# 12_MEM_DDR3.net
KiCad netlist of a schematic drawn in Altium Designer
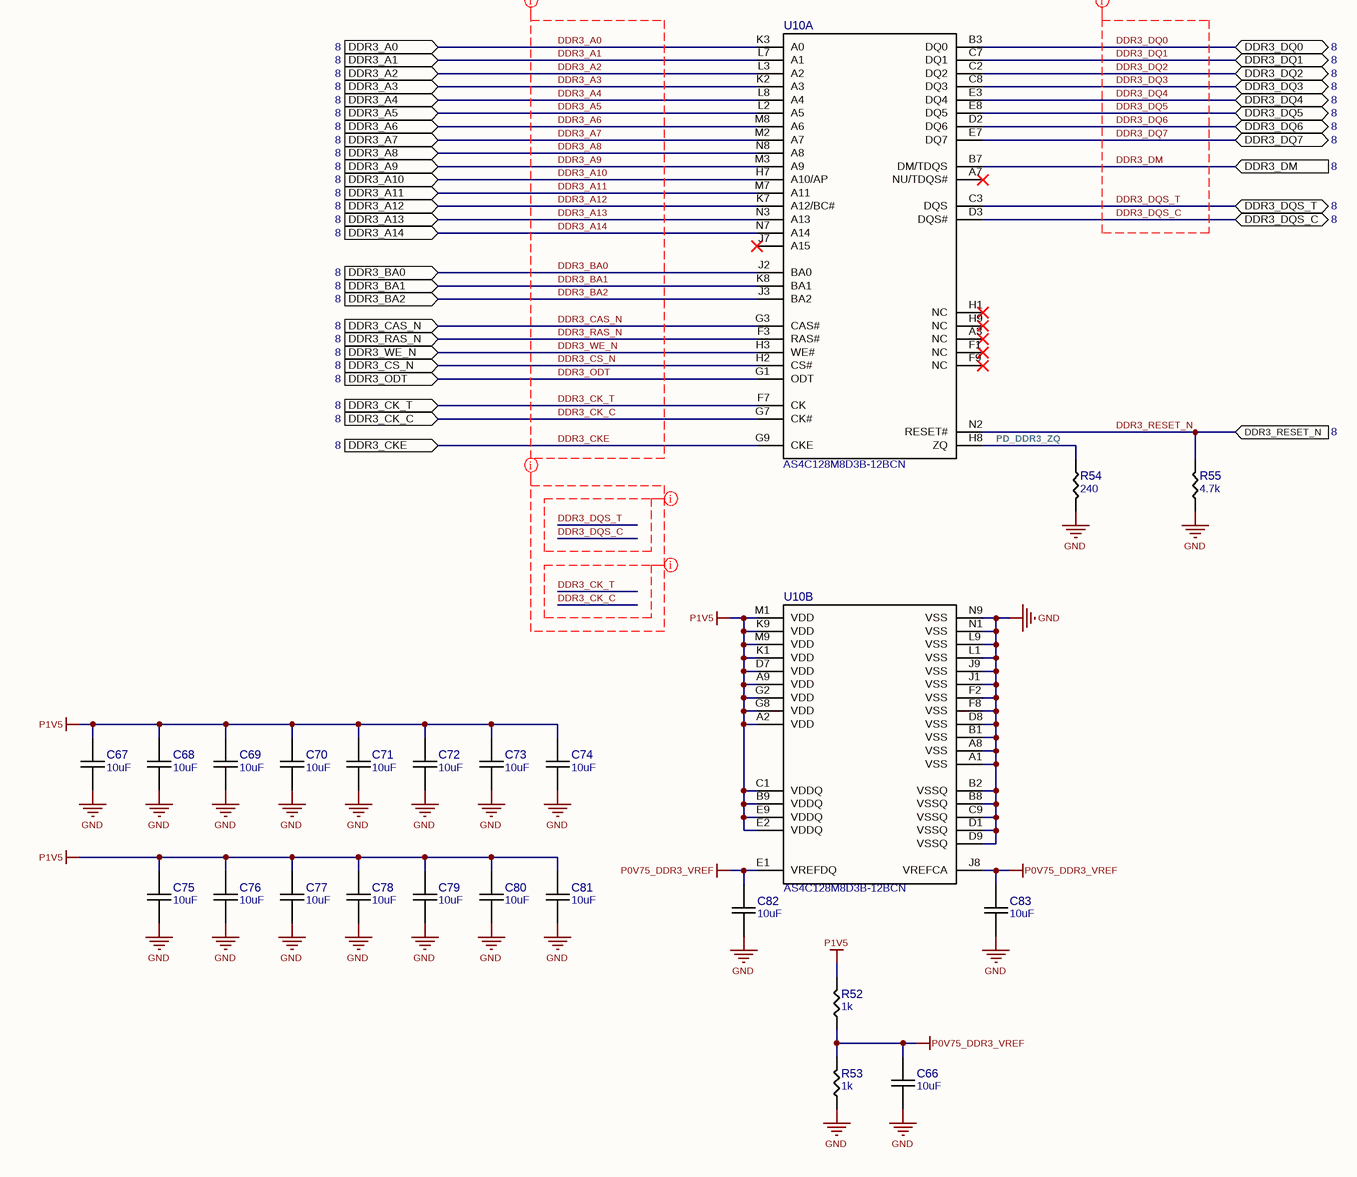
[diagram p0: 12_MEM_DDR3.SchDoc]

(export (version "E")
  (design (tool "Eeschema 10.0.6"))
  (components
    (comp (ref "C66")
      (value "10uF")
      (footprint "CAPC1005X06N")
      (description "CAP CER 10UF 6.3V X5R 0402")
      (fields (field (name "PART NUMBER") "GRM155R60J106ME47D") (field (name "VOLTAGE") "6.3V"))
      (libsource (lib "Database") (part "Capacitor"))
    )
    (comp (ref "C67")
      (value "10uF")
      (footprint "CAPC1005X06N")
      (description "CAP CER 10UF 6.3V X5R 0402")
      (fields (field (name "PART NUMBER") "GRM155R60J106ME47D") (field (name "VOLTAGE") "6.3V"))
      (libsource (lib "Database") (part "Capacitor"))
    )
    (comp (ref "C68")
      (value "10uF")
      (footprint "CAPC1005X06N")
      (description "CAP CER 10UF 6.3V X5R 0402")
      (fields (field (name "PART NUMBER") "GRM155R60J106ME47D") (field (name "VOLTAGE") "6.3V"))
      (libsource (lib "Database") (part "Capacitor"))
    )
    (comp (ref "C69")
      (value "10uF")
      (footprint "CAPC1005X06N")
      (description "CAP CER 10UF 6.3V X5R 0402")
      (fields (field (name "PART NUMBER") "GRM155R60J106ME47D") (field (name "VOLTAGE") "6.3V"))
      (libsource (lib "Database") (part "Capacitor"))
    )
    (comp (ref "C70")
      (value "10uF")
      (footprint "CAPC1005X06N")
      (description "CAP CER 10UF 6.3V X5R 0402")
      (fields (field (name "PART NUMBER") "GRM155R60J106ME47D") (field (name "VOLTAGE") "6.3V"))
      (libsource (lib "Database") (part "Capacitor"))
    )
    (comp (ref "C71")
      (value "10uF")
      (footprint "CAPC1005X06N")
      (description "CAP CER 10UF 6.3V X5R 0402")
      (fields (field (name "PART NUMBER") "GRM155R60J106ME47D") (field (name "VOLTAGE") "6.3V"))
      (libsource (lib "Database") (part "Capacitor"))
    )
    (comp (ref "C72")
      (value "10uF")
      (footprint "CAPC1005X06N")
      (description "CAP CER 10UF 6.3V X5R 0402")
      (fields (field (name "PART NUMBER") "GRM155R60J106ME47D") (field (name "VOLTAGE") "6.3V"))
      (libsource (lib "Database") (part "Capacitor"))
    )
    (comp (ref "C73")
      (value "10uF")
      (footprint "CAPC1005X06N")
      (description "CAP CER 10UF 6.3V X5R 0402")
      (fields (field (name "PART NUMBER") "GRM155R60J106ME47D") (field (name "VOLTAGE") "6.3V"))
      (libsource (lib "Database") (part "Capacitor"))
    )
    (comp (ref "C74")
      (value "10uF")
      (footprint "CAPC1005X06N")
      (description "CAP CER 10UF 6.3V X5R 0402")
      (fields (field (name "PART NUMBER") "GRM155R60J106ME47D") (field (name "VOLTAGE") "6.3V"))
      (libsource (lib "Database") (part "Capacitor"))
    )
    (comp (ref "C75")
      (value "10uF")
      (footprint "CAPC1005X06N")
      (description "CAP CER 10UF 6.3V X5R 0402")
      (fields (field (name "PART NUMBER") "GRM155R60J106ME47D") (field (name "VOLTAGE") "6.3V"))
      (libsource (lib "Database") (part "Capacitor"))
    )
    (comp (ref "C76")
      (value "10uF")
      (footprint "CAPC1005X06N")
      (description "CAP CER 10UF 6.3V X5R 0402")
      (fields (field (name "PART NUMBER") "GRM155R60J106ME47D") (field (name "VOLTAGE") "6.3V"))
      (libsource (lib "Database") (part "Capacitor"))
    )
    (comp (ref "C77")
      (value "10uF")
      (footprint "CAPC1005X06N")
      (description "CAP CER 10UF 6.3V X5R 0402")
      (fields (field (name "PART NUMBER") "GRM155R60J106ME47D") (field (name "VOLTAGE") "6.3V"))
      (libsource (lib "Database") (part "Capacitor"))
    )
    (comp (ref "C78")
      (value "10uF")
      (footprint "CAPC1005X06N")
      (description "CAP CER 10UF 6.3V X5R 0402")
      (fields (field (name "PART NUMBER") "GRM155R60J106ME47D") (field (name "VOLTAGE") "6.3V"))
      (libsource (lib "Database") (part "Capacitor"))
    )
    (comp (ref "C79")
      (value "10uF")
      (footprint "CAPC1005X06N")
      (description "CAP CER 10UF 6.3V X5R 0402")
      (fields (field (name "PART NUMBER") "GRM155R60J106ME47D") (field (name "VOLTAGE") "6.3V"))
      (libsource (lib "Database") (part "Capacitor"))
    )
    (comp (ref "C80")
      (value "10uF")
      (footprint "CAPC1005X06N")
      (description "CAP CER 10UF 6.3V X5R 0402")
      (fields (field (name "PART NUMBER") "GRM155R60J106ME47D") (field (name "VOLTAGE") "6.3V"))
      (libsource (lib "Database") (part "Capacitor"))
    )
    (comp (ref "C81")
      (value "10uF")
      (footprint "CAPC1005X06N")
      (description "CAP CER 10UF 6.3V X5R 0402")
      (fields (field (name "PART NUMBER") "GRM155R60J106ME47D") (field (name "VOLTAGE") "6.3V"))
      (libsource (lib "Database") (part "Capacitor"))
    )
    (comp (ref "C82")
      (value "10uF")
      (footprint "CAPC1005X06N")
      (description "CAP CER 10UF 6.3V X5R 0402")
      (fields (field (name "PART NUMBER") "GRM155R60J106ME47D") (field (name "VOLTAGE") "6.3V"))
      (libsource (lib "Database") (part "Capacitor"))
    )
    (comp (ref "C83")
      (value "10uF")
      (footprint "CAPC1005X06N")
      (description "CAP CER 10UF 6.3V X5R 0402")
      (fields (field (name "PART NUMBER") "GRM155R60J106ME47D") (field (name "VOLTAGE") "6.3V"))
      (libsource (lib "Database") (part "Capacitor"))
    )
    (comp (ref "R52")
      (value "1k")
      (footprint "RESC1005X03N")
      (description "RES SMD 1K OHM 1% 1/16W 0402")
      (fields (field (name "PART NUMBER") "RC0402FR-071KL"))
      (libsource (lib "Database") (part "Resistor_ENG"))
    )
    (comp (ref "R53")
      (value "1k")
      (footprint "RESC1005X03N")
      (description "RES SMD 1K OHM 1% 1/16W 0402")
      (fields (field (name "PART NUMBER") "RC0402FR-071KL"))
      (libsource (lib "Database") (part "Resistor_ENG"))
    )
    (comp (ref "R54")
      (value "240")
      (footprint "RESC1005X03N")
      (description "RES SMD 240 OHM 1% 1/16W 0402")
      (fields (field (name "PART NUMBER") "RC0402FR-07240RL"))
      (libsource (lib "Database") (part "Resistor_ENG"))
    )
    (comp (ref "R55")
      (value "4.7k")
      (footprint "RESC1005X03N")
      (description "RES SMD 4.7K OHM 1% 1/16W 0402")
      (fields (field (name "PART NUMBER") "RC0402FR-074K7L"))
      (libsource (lib "Database") (part "Resistor_ENG"))
    )
    (comp (ref "U10")
      (value "AS4C128M8D3B-12BCN")
      (footprint "BGA78C80P9X13_800X1050X100")
      (description "IC DRAM 1GBIT PARALLEL 78FBGA")
      (libsource (lib "") (part "JEDEC_DDR3_78_PIN_1"))
    )
  )
  (nets
    (net (code "1") (name "/DDR3_A0") (class "Default")
      (node (ref "U10") (pin "K3") (pinfunction "A0_K3") (pintype "passive"))
    )
    (net (code "2") (name "/DDR3_A1") (class "Default")
      (node (ref "U10") (pin "L7") (pinfunction "A1_L7") (pintype "passive"))
    )
    (net (code "3") (name "/DDR3_A2") (class "Default")
      (node (ref "U10") (pin "L3") (pinfunction "A2_L3") (pintype "passive"))
    )
    (net (code "4") (name "/DDR3_A3") (class "Default")
      (node (ref "U10") (pin "K2") (pinfunction "A3_K2") (pintype "passive"))
    )
    (net (code "5") (name "/DDR3_A4") (class "Default")
      (node (ref "U10") (pin "L8") (pinfunction "A4_L8") (pintype "passive"))
    )
    (net (code "6") (name "/DDR3_A5") (class "Default")
      (node (ref "U10") (pin "L2") (pinfunction "A5_L2") (pintype "passive"))
    )
    (net (code "7") (name "/DDR3_A6") (class "Default")
      (node (ref "U10") (pin "M8") (pinfunction "A6_M8") (pintype "passive"))
    )
    (net (code "8") (name "/DDR3_A7") (class "Default")
      (node (ref "U10") (pin "M2") (pinfunction "A7_M2") (pintype "passive"))
    )
    (net (code "9") (name "/DDR3_A8") (class "Default")
      (node (ref "U10") (pin "N8") (pinfunction "A8_N8") (pintype "passive"))
    )
    (net (code "10") (name "/DDR3_A9") (class "Default")
      (node (ref "U10") (pin "M3") (pinfunction "A9_M3") (pintype "passive"))
    )
    (net (code "11") (name "/DDR3_A10") (class "Default")
      (node (ref "U10") (pin "H7") (pinfunction "A10/AP_H7") (pintype "passive"))
    )
    (net (code "12") (name "/DDR3_A11") (class "Default")
      (node (ref "U10") (pin "M7") (pinfunction "A11_M7") (pintype "passive"))
    )
    (net (code "13") (name "/DDR3_A12") (class "Default")
      (node (ref "U10") (pin "K7") (pinfunction "A12/BC#_K7") (pintype "passive"))
    )
    (net (code "14") (name "/DDR3_A13") (class "Default")
      (node (ref "U10") (pin "N3") (pinfunction "A13_N3") (pintype "passive"))
    )
    (net (code "15") (name "/DDR3_A14") (class "Default")
      (node (ref "U10") (pin "N7") (pinfunction "A14_N7") (pintype "passive"))
    )
    (net (code "16") (name "/DDR3_BA0") (class "Default")
      (node (ref "U10") (pin "J2") (pinfunction "BA0_J2") (pintype "passive"))
    )
    (net (code "17") (name "/DDR3_BA1") (class "Default")
      (node (ref "U10") (pin "K8") (pinfunction "BA1_K8") (pintype "passive"))
    )
    (net (code "18") (name "/DDR3_BA2") (class "Default")
      (node (ref "U10") (pin "J3") (pinfunction "BA2_J3") (pintype "passive"))
    )
    (net (code "19") (name "/DDR3_CAS_N") (class "Default")
      (node (ref "U10") (pin "G3") (pinfunction "CAS#_G3") (pintype "passive"))
    )
    (net (code "20") (name "/DDR3_CKE") (class "Default")
      (node (ref "U10") (pin "G9") (pinfunction "CKE_G9") (pintype "passive"))
    )
    (net (code "21") (name "/DDR3_CK_C") (class "Default")
      (node (ref "U10") (pin "G7") (pinfunction "CK#_G7") (pintype "passive"))
    )
    (net (code "22") (name "/DDR3_CK_T") (class "Default")
      (node (ref "U10") (pin "F7") (pinfunction "CK_F7") (pintype "passive"))
    )
    (net (code "23") (name "/DDR3_CS_N") (class "Default")
      (node (ref "U10") (pin "H2") (pinfunction "CS#_H2") (pintype "passive"))
    )
    (net (code "24") (name "/DDR3_DM") (class "Default")
      (node (ref "U10") (pin "B7") (pinfunction "DM/TDQS_B7") (pintype "passive"))
    )
    (net (code "25") (name "/DDR3_DQ0") (class "Default")
      (node (ref "U10") (pin "B3") (pinfunction "DQ0_B3") (pintype "passive"))
    )
    (net (code "26") (name "/DDR3_DQ1") (class "Default")
      (node (ref "U10") (pin "C7") (pinfunction "DQ1_C7") (pintype "passive"))
    )
    (net (code "27") (name "/DDR3_DQ2") (class "Default")
      (node (ref "U10") (pin "C2") (pinfunction "DQ2_C2") (pintype "passive"))
    )
    (net (code "28") (name "/DDR3_DQ3") (class "Default")
      (node (ref "U10") (pin "C8") (pinfunction "DQ3_C8") (pintype "passive"))
    )
    (net (code "29") (name "/DDR3_DQ4") (class "Default")
      (node (ref "U10") (pin "E3") (pinfunction "DQ4_E3") (pintype "passive"))
    )
    (net (code "30") (name "/DDR3_DQ5") (class "Default")
      (node (ref "U10") (pin "E8") (pinfunction "DQ5_E8") (pintype "passive"))
    )
    (net (code "31") (name "/DDR3_DQ6") (class "Default")
      (node (ref "U10") (pin "D2") (pinfunction "DQ6_D2") (pintype "passive"))
    )
    (net (code "32") (name "/DDR3_DQ7") (class "Default")
      (node (ref "U10") (pin "E7") (pinfunction "DQ7_E7") (pintype "passive"))
    )
    (net (code "33") (name "/DDR3_DQS_C") (class "Default")
      (node (ref "U10") (pin "D3") (pinfunction "DQS#_D3") (pintype "passive"))
    )
    (net (code "34") (name "/DDR3_DQS_T") (class "Default")
      (node (ref "U10") (pin "C3") (pinfunction "DQS_C3") (pintype "passive"))
    )
    (net (code "35") (name "/DDR3_ODT") (class "Default")
      (node (ref "U10") (pin "G1") (pinfunction "ODT_G1") (pintype "passive"))
    )
    (net (code "36") (name "/DDR3_RAS_N") (class "Default")
      (node (ref "U10") (pin "F3") (pinfunction "RAS#_F3") (pintype "passive"))
    )
    (net (code "37") (name "/DDR3_RESET_N") (class "Default")
      (node (ref "R55") (pin "2") (pinfunction "2_2") (pintype "passive"))
      (node (ref "U10") (pin "N2") (pinfunction "RESET#_N2") (pintype "passive"))
    )
    (net (code "38") (name "/DDR3_WE_N") (class "Default")
      (node (ref "U10") (pin "H3") (pinfunction "WE#_H3") (pintype "passive"))
    )
    (net (code "39") (name "/PD_DDR3_ZQ") (class "Default")
      (node (ref "R54") (pin "1") (pinfunction "1_1") (pintype "passive"))
      (node (ref "U10") (pin "H8") (pinfunction "ZQ_H8") (pintype "passive"))
    )
    (net (code "40") (name "GND") (class "Default")
      (node (ref "C66") (pin "1") (pinfunction "1_1") (pintype "passive"))
      (node (ref "C67") (pin "1") (pinfunction "1_1") (pintype "passive"))
      (node (ref "C68") (pin "1") (pinfunction "1_1") (pintype "passive"))
      (node (ref "C69") (pin "1") (pinfunction "1_1") (pintype "passive"))
      (node (ref "C70") (pin "1") (pinfunction "1_1") (pintype "passive"))
      (node (ref "C71") (pin "1") (pinfunction "1_1") (pintype "passive"))
      (node (ref "C72") (pin "1") (pinfunction "1_1") (pintype "passive"))
      (node (ref "C73") (pin "1") (pinfunction "1_1") (pintype "passive"))
      (node (ref "C74") (pin "1") (pinfunction "1_1") (pintype "passive"))
      (node (ref "C75") (pin "1") (pinfunction "1_1") (pintype "passive"))
      (node (ref "C76") (pin "1") (pinfunction "1_1") (pintype "passive"))
      (node (ref "C77") (pin "1") (pinfunction "1_1") (pintype "passive"))
      (node (ref "C78") (pin "1") (pinfunction "1_1") (pintype "passive"))
      (node (ref "C79") (pin "1") (pinfunction "1_1") (pintype "passive"))
      (node (ref "C80") (pin "1") (pinfunction "1_1") (pintype "passive"))
      (node (ref "C81") (pin "1") (pinfunction "1_1") (pintype "passive"))
      (node (ref "C82") (pin "1") (pinfunction "1_1") (pintype "passive"))
      (node (ref "C83") (pin "1") (pinfunction "1_1") (pintype "passive"))
      (node (ref "R53") (pin "1") (pinfunction "1_1") (pintype "passive"))
      (node (ref "R54") (pin "2") (pinfunction "2_2") (pintype "passive"))
      (node (ref "R55") (pin "1") (pinfunction "1_1") (pintype "passive"))
      (node (ref "U10") (pin "A1") (pinfunction "VSS_A1") (pintype "passive"))
      (node (ref "U10") (pin "A8") (pinfunction "VSS_A8") (pintype "passive"))
      (node (ref "U10") (pin "B1") (pinfunction "VSS_B1") (pintype "passive"))
      (node (ref "U10") (pin "B2") (pinfunction "VSSQ_B2") (pintype "passive"))
      (node (ref "U10") (pin "B8") (pinfunction "VSSQ_B8") (pintype "passive"))
      (node (ref "U10") (pin "C9") (pinfunction "VSSQ_C9") (pintype "passive"))
      (node (ref "U10") (pin "D1") (pinfunction "VSSQ_D1") (pintype "passive"))
      (node (ref "U10") (pin "D8") (pinfunction "VSS_D8") (pintype "passive"))
      (node (ref "U10") (pin "D9") (pinfunction "VSSQ_D9") (pintype "passive"))
      (node (ref "U10") (pin "F2") (pinfunction "VSS_F2") (pintype "passive"))
      (node (ref "U10") (pin "F8") (pinfunction "VSS_F8") (pintype "passive"))
      (node (ref "U10") (pin "J1") (pinfunction "VSS_J1") (pintype "passive"))
      (node (ref "U10") (pin "J9") (pinfunction "VSS_J9") (pintype "passive"))
      (node (ref "U10") (pin "L1") (pinfunction "VSS_L1") (pintype "passive"))
      (node (ref "U10") (pin "L9") (pinfunction "VSS_L9") (pintype "passive"))
      (node (ref "U10") (pin "N1") (pinfunction "VSS_N1") (pintype "passive"))
      (node (ref "U10") (pin "N9") (pinfunction "VSS_N9") (pintype "passive"))
    )
    (net (code "41") (name "P0V75_DDR3_VREF") (class "Default")
      (node (ref "C66") (pin "2") (pinfunction "2_2") (pintype "passive"))
      (node (ref "C82") (pin "2") (pinfunction "2_2") (pintype "passive"))
      (node (ref "C83") (pin "2") (pinfunction "2_2") (pintype "passive"))
      (node (ref "R52") (pin "1") (pinfunction "1_1") (pintype "passive"))
      (node (ref "R53") (pin "2") (pinfunction "2_2") (pintype "passive"))
      (node (ref "U10") (pin "E1") (pinfunction "VREFDQ_E1") (pintype "passive"))
      (node (ref "U10") (pin "J8") (pinfunction "VREFCA_J8") (pintype "passive"))
    )
    (net (code "42") (name "P1V5") (class "Default")
      (node (ref "C67") (pin "2") (pinfunction "2_2") (pintype "passive"))
      (node (ref "C68") (pin "2") (pinfunction "2_2") (pintype "passive"))
      (node (ref "C69") (pin "2") (pinfunction "2_2") (pintype "passive"))
      (node (ref "C70") (pin "2") (pinfunction "2_2") (pintype "passive"))
      (node (ref "C71") (pin "2") (pinfunction "2_2") (pintype "passive"))
      (node (ref "C72") (pin "2") (pinfunction "2_2") (pintype "passive"))
      (node (ref "C73") (pin "2") (pinfunction "2_2") (pintype "passive"))
      (node (ref "C74") (pin "2") (pinfunction "2_2") (pintype "passive"))
      (node (ref "C75") (pin "2") (pinfunction "2_2") (pintype "passive"))
      (node (ref "C76") (pin "2") (pinfunction "2_2") (pintype "passive"))
      (node (ref "C77") (pin "2") (pinfunction "2_2") (pintype "passive"))
      (node (ref "C78") (pin "2") (pinfunction "2_2") (pintype "passive"))
      (node (ref "C79") (pin "2") (pinfunction "2_2") (pintype "passive"))
      (node (ref "C80") (pin "2") (pinfunction "2_2") (pintype "passive"))
      (node (ref "C81") (pin "2") (pinfunction "2_2") (pintype "passive"))
      (node (ref "R52") (pin "2") (pinfunction "2_2") (pintype "passive"))
      (node (ref "U10") (pin "A2") (pinfunction "VDD_A2") (pintype "passive"))
      (node (ref "U10") (pin "A9") (pinfunction "VDD_A9") (pintype "passive"))
      (node (ref "U10") (pin "B9") (pinfunction "VDDQ_B9") (pintype "passive"))
      (node (ref "U10") (pin "C1") (pinfunction "VDDQ_C1") (pintype "passive"))
      (node (ref "U10") (pin "D7") (pinfunction "VDD_D7") (pintype "passive"))
      (node (ref "U10") (pin "E2") (pinfunction "VDDQ_E2") (pintype "passive"))
      (node (ref "U10") (pin "E9") (pinfunction "VDDQ_E9") (pintype "passive"))
      (node (ref "U10") (pin "G2") (pinfunction "VDD_G2") (pintype "passive"))
      (node (ref "U10") (pin "G8") (pinfunction "VDD_G8") (pintype "passive"))
      (node (ref "U10") (pin "K1") (pinfunction "VDD_K1") (pintype "passive"))
      (node (ref "U10") (pin "K9") (pinfunction "VDD_K9") (pintype "passive"))
      (node (ref "U10") (pin "M1") (pinfunction "VDD_M1") (pintype "passive"))
      (node (ref "U10") (pin "M9") (pinfunction "VDD_M9") (pintype "passive"))
    )
    (net (code "43") (name "unconnected-(U10A-A15-PadJ7)") (class "Default")
      (node (ref "U10") (pin "J7") (pinfunction "A15_J7") (pintype "passive+no_connect"))
    )
    (net (code "44") (name "unconnected-(U10A-NC-PadA3)") (class "Default")
      (node (ref "U10") (pin "A3") (pinfunction "NC_A3") (pintype "passive+no_connect"))
    )
    (net (code "45") (name "unconnected-(U10A-NC-PadF1)") (class "Default")
      (node (ref "U10") (pin "F1") (pinfunction "NC_F1") (pintype "passive+no_connect"))
    )
    (net (code "46") (name "unconnected-(U10A-NC-PadF9)") (class "Default")
      (node (ref "U10") (pin "F9") (pinfunction "NC_F9") (pintype "passive+no_connect"))
    )
    (net (code "47") (name "unconnected-(U10A-NC-PadH1)") (class "Default")
      (node (ref "U10") (pin "H1") (pinfunction "NC_H1") (pintype "passive+no_connect"))
    )
    (net (code "48") (name "unconnected-(U10A-NC-PadH9)") (class "Default")
      (node (ref "U10") (pin "H9") (pinfunction "NC_H9") (pintype "passive+no_connect"))
    )
    (net (code "49") (name "unconnected-(U10A-NU{slash}TDQS#-PadA7)") (class "Default")
      (node (ref "U10") (pin "A7") (pinfunction "NU/TDQS#_A7") (pintype "passive+no_connect"))
    )
  )
)
